# PowerDistReva.net
KiCad netlist of a schematic drawn in Altium Designer
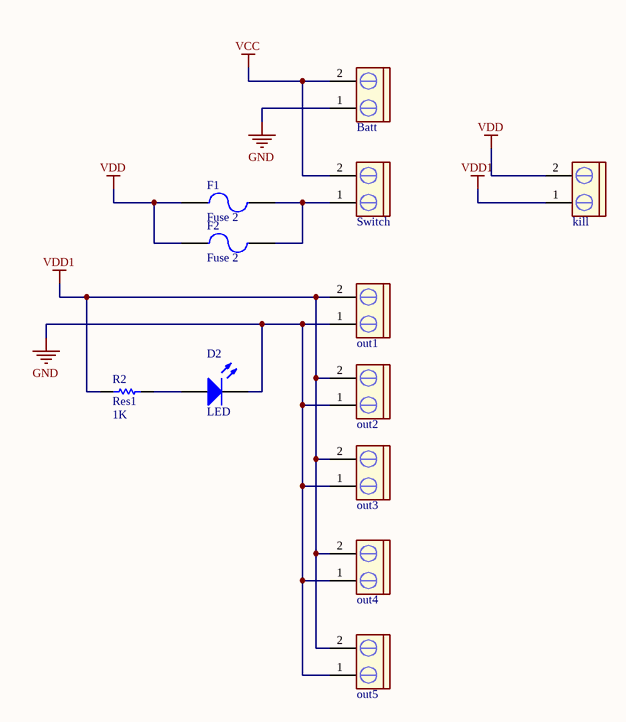
[diagram p0: PowerDistReva.SchDoc]

(export (version "E")
  (design (tool "Eeschema 10.0.6"))
  (components
    (comp (ref "Batt")
      (value "CON2 pin blue")
      (footprint "My_CN2")
      (description "Connector blue screw")
      (libsource (lib "Mylib") (part "CON2 pin blue"))
    )
    (comp (ref "D2")
      (value "LED")
      (footprint "My_LED3MM")
      (description "Typical INFRARED GaAs LED")
      (fields (field (name "PUBLISHER") "Altium Limited"))
      (libsource (lib "Mylib") (part "LED"))
    )
    (comp (ref "F1")
      (value "Fuse 2")
      (footprint "FUSE:PCBComponent_1")
      (description "Fuse")
      (fields (field (name "PUBLISHER") "Altium Limited"))
      (libsource (lib "Miscellaneous Devices") (part "Fuse 2"))
    )
    (comp (ref "F2")
      (value "Fuse 2")
      (footprint "PCBComponent_1")
      (description "Fuse")
      (fields (field (name "PUBLISHER") "Altium Limited"))
      (libsource (lib "Miscellaneous Devices") (part "Fuse 2"))
    )
    (comp (ref "kill")
      (value "CON2 pin blue")
      (footprint "My_CN2")
      (description "Connector blue screw")
      (libsource (lib "Mylib") (part "CON2 pin blue"))
    )
    (comp (ref "out1")
      (value "CON2 pin blue")
      (footprint "My_CN2")
      (description "Connector blue screw")
      (libsource (lib "Mylib") (part "CON2 pin blue"))
    )
    (comp (ref "out2")
      (value "CON2 pin blue")
      (footprint "My_CN2")
      (description "Connector blue screw")
      (libsource (lib "Mylib") (part "CON2 pin blue"))
    )
    (comp (ref "out3")
      (value "CON2 pin blue")
      (footprint "My_CN2")
      (description "Connector blue screw")
      (libsource (lib "Mylib") (part "CON2 pin blue"))
    )
    (comp (ref "out4")
      (value "CON2 pin blue")
      (footprint "My_CN2")
      (description "Connector blue screw")
      (libsource (lib "Mylib") (part "CON2 pin blue"))
    )
    (comp (ref "out5")
      (value "CON2 pin blue")
      (footprint "My_CN2")
      (description "Connector blue screw")
      (libsource (lib "Mylib") (part "CON2 pin blue"))
    )
    (comp (ref "R2")
      (value "Res1")
      (footprint "AXIAL-0.3")
      (description "Resistor")
      (fields (field (name "ALTIUM_VALUE") "1K") (field (name "PUBLISHER") "Altium Limited"))
      (libsource (lib "Miscellaneous Devices") (part "Res1"))
    )
    (comp (ref "Switch")
      (value "CON2 pin blue")
      (footprint "My_CN2")
      (description "Connector blue screw")
      (libsource (lib "Mylib") (part "CON2 pin blue"))
    )
  )
  (nets
    (net (code "1") (name "GND") (class "Default")
      (node (ref "Batt") (pin "1") (pinfunction "1_1") (pintype "passive"))
      (node (ref "D2") (pin "K") (pinfunction "K_K") (pintype "passive"))
      (node (ref "out1") (pin "1") (pinfunction "1_1") (pintype "passive"))
      (node (ref "out2") (pin "1") (pinfunction "1_1") (pintype "passive"))
      (node (ref "out3") (pin "1") (pinfunction "1_1") (pintype "passive"))
      (node (ref "out4") (pin "1") (pinfunction "1_1") (pintype "passive"))
      (node (ref "out5") (pin "1") (pinfunction "1_1") (pintype "passive"))
    )
    (net (code "2") (name "Net-(D2-PadA)") (class "Default")
      (node (ref "D2") (pin "A") (pinfunction "A_A") (pintype "passive"))
      (node (ref "R2") (pin "2") (pinfunction "2_2") (pintype "passive"))
    )
    (net (code "3") (name "Net-(F1-Pad2)") (class "Default")
      (node (ref "F1") (pin "2") (pinfunction "2_2") (pintype "passive"))
      (node (ref "F2") (pin "2") (pinfunction "2_2") (pintype "passive"))
      (node (ref "Switch") (pin "1") (pinfunction "1_1") (pintype "passive"))
    )
    (net (code "4") (name "VCC") (class "Default")
      (node (ref "Batt") (pin "2") (pinfunction "2_2") (pintype "passive"))
      (node (ref "Switch") (pin "2") (pinfunction "2_2") (pintype "passive"))
    )
    (net (code "5") (name "VDD") (class "Default")
      (node (ref "F1") (pin "1") (pinfunction "1_1") (pintype "passive"))
      (node (ref "F2") (pin "1") (pinfunction "1_1") (pintype "passive"))
      (node (ref "kill") (pin "2") (pinfunction "2_2") (pintype "passive"))
    )
    (net (code "6") (name "VDD1") (class "Default")
      (node (ref "R2") (pin "1") (pinfunction "1_1") (pintype "passive"))
      (node (ref "kill") (pin "1") (pinfunction "1_1") (pintype "passive"))
      (node (ref "out1") (pin "2") (pinfunction "2_2") (pintype "passive"))
      (node (ref "out2") (pin "2") (pinfunction "2_2") (pintype "passive"))
      (node (ref "out3") (pin "2") (pinfunction "2_2") (pintype "passive"))
      (node (ref "out4") (pin "2") (pinfunction "2_2") (pintype "passive"))
      (node (ref "out5") (pin "2") (pinfunction "2_2") (pintype "passive"))
    )
  )
)
